# pcb.net
KiCad netlist of a schematic drawn in EAGLE
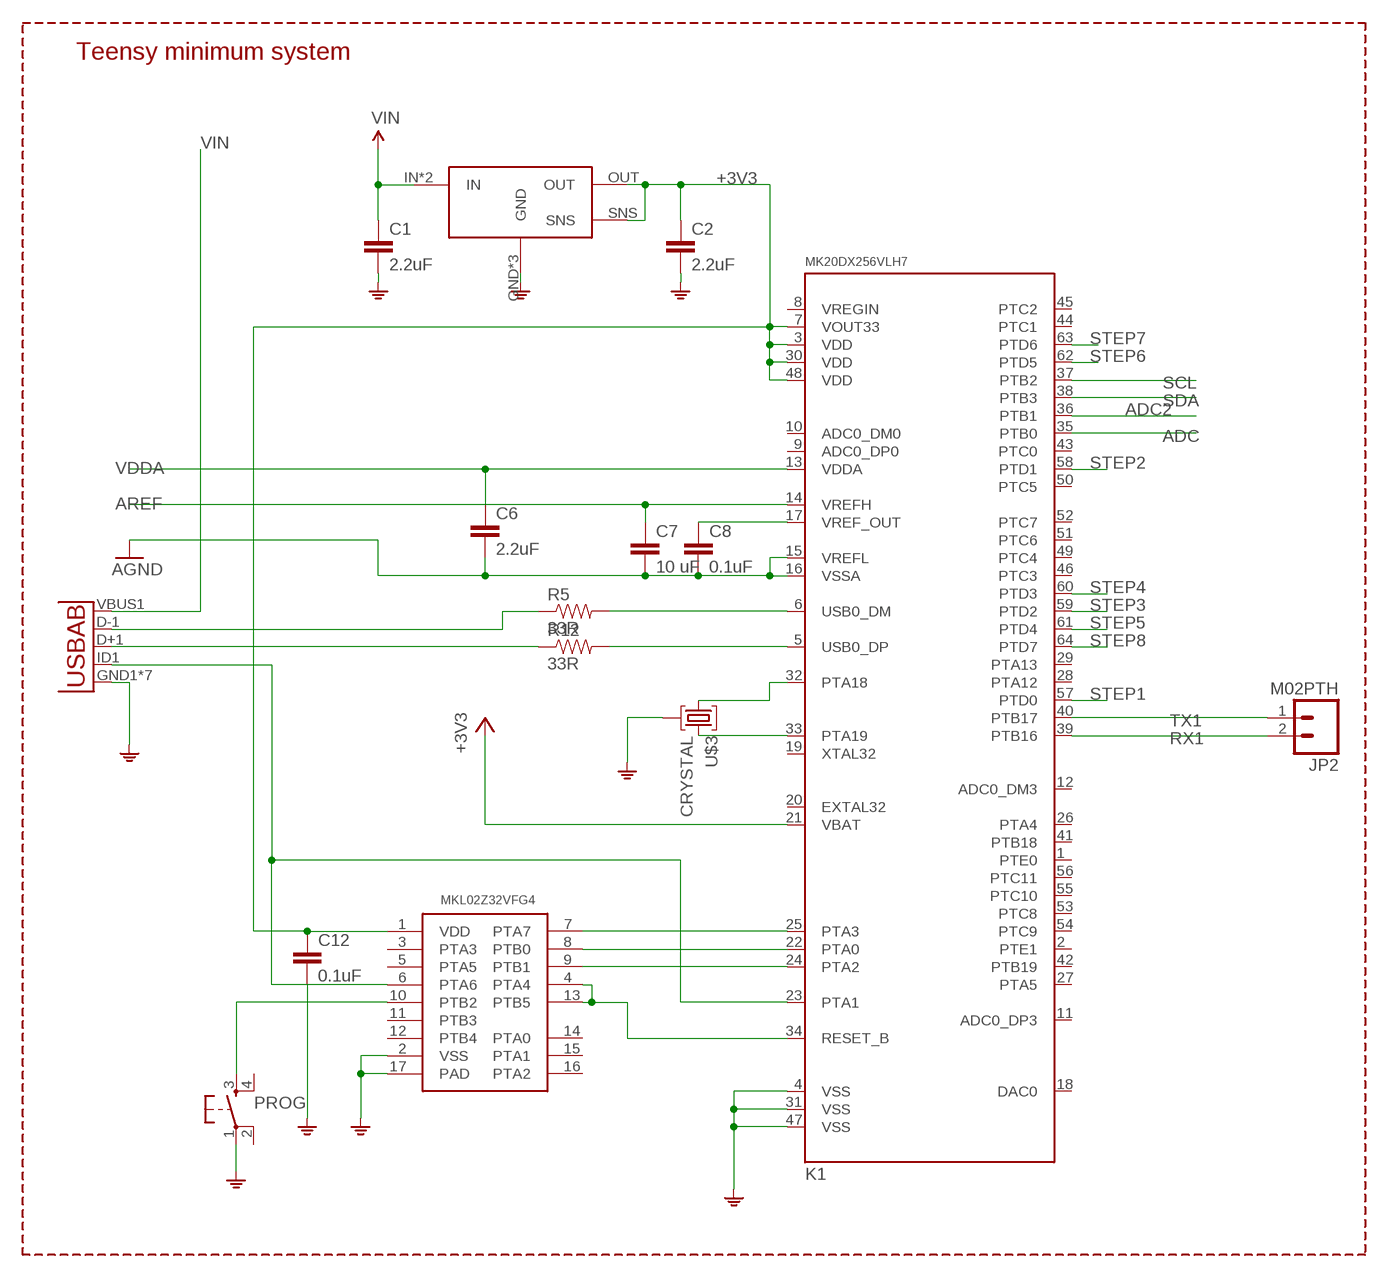
[diagram p0: schematic, sheet 1, part 1 of 2]
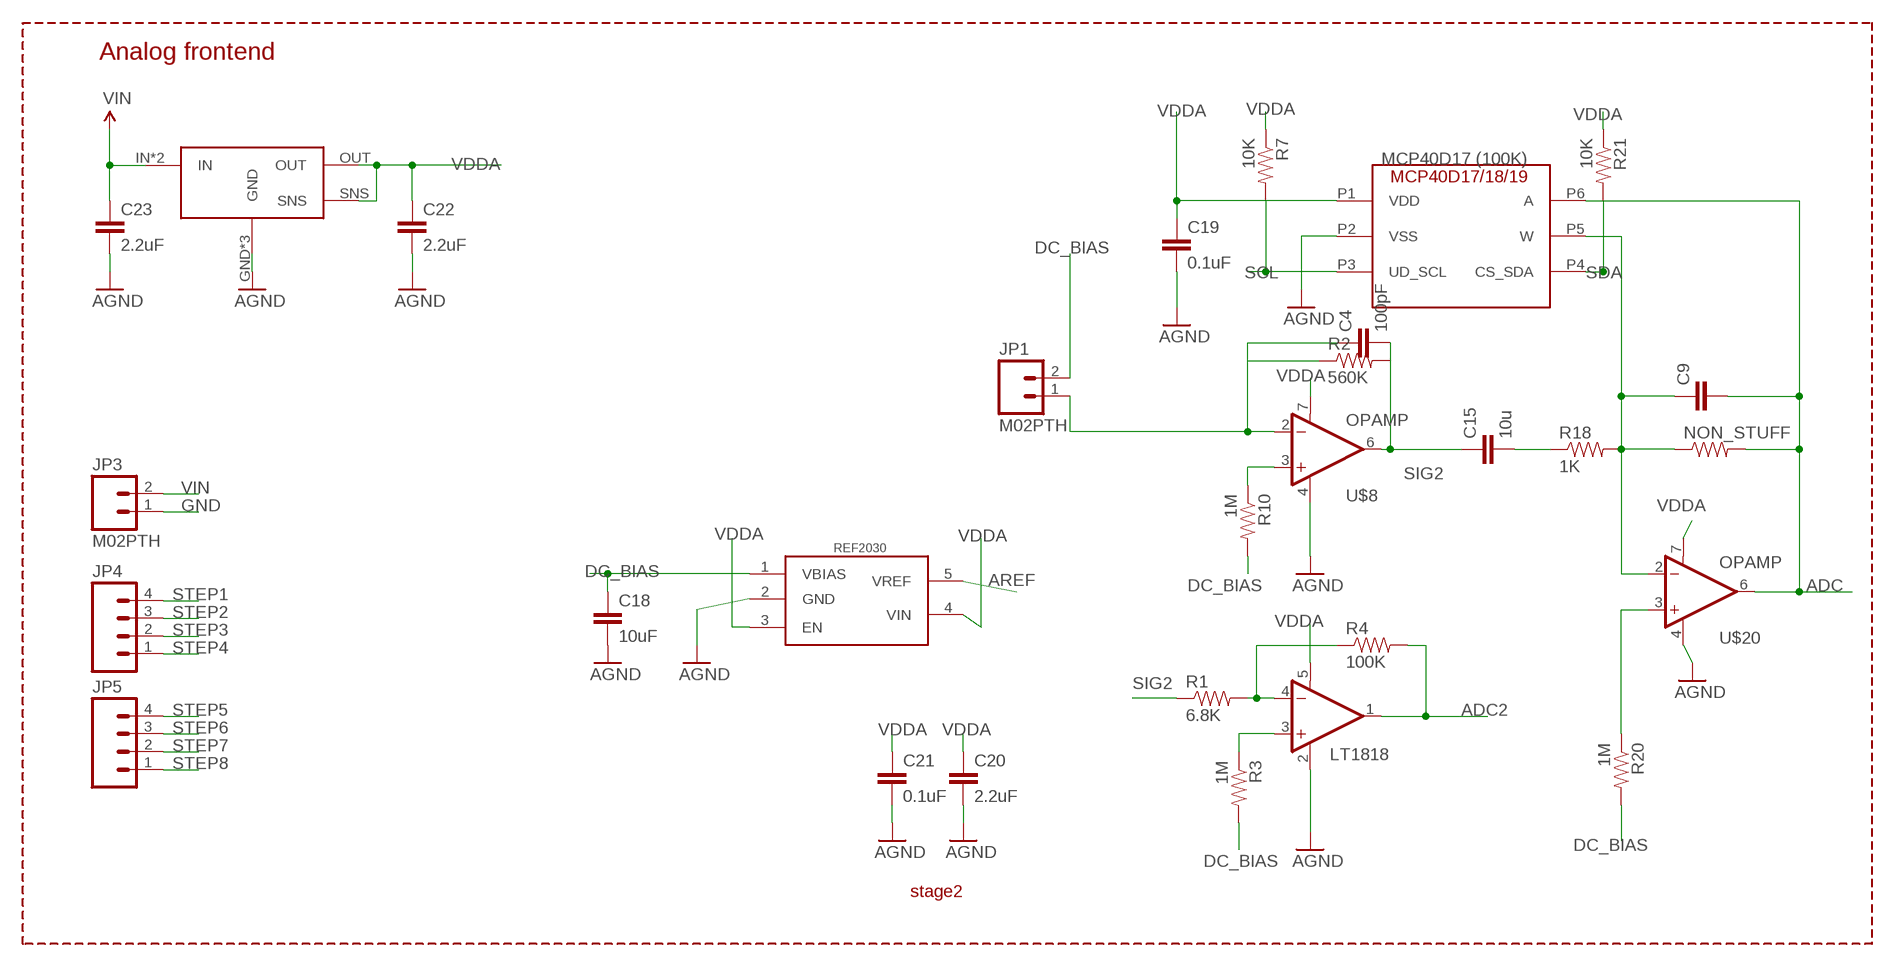
[diagram p1: schematic, sheet 1, part 2 of 2]

(export (version "E")
  (design (tool "Eeschema 10.0.6"))
  (components
    (comp (ref "C1")
      (value "2.2uF")
      (footprint "eagle-import:0402-CAP")
      (libsource (lib "eagle-import") (part "0.1UF-16V(+-10%)(0402)"))
    )
    (comp (ref "C2")
      (value "2.2uF")
      (footprint "eagle-import:0402-CAP")
      (libsource (lib "eagle-import") (part "0.1UF-16V(+-10%)(0402)"))
    )
    (comp (ref "C4")
      (value "100pF")
      (footprint "eagle-import:0402-CAP")
      (libsource (lib "eagle-import") (part "0.1UF-16V(+-10%)(0402)"))
    )
    (comp (ref "C6")
      (value "2.2uF")
      (footprint "eagle-import:0402-CAP")
      (libsource (lib "eagle-import") (part "0.1UF-16V(+-10%)(0402)"))
    )
    (comp (ref "C7")
      (value "10 uF")
      (footprint "eagle-import:0402-CAP")
      (libsource (lib "eagle-import") (part "0.1UF-16V(+-10%)(0402)"))
    )
    (comp (ref "C8")
      (value "0.1uF")
      (footprint "eagle-import:0402-CAP")
      (libsource (lib "eagle-import") (part "0.1UF-16V(+-10%)(0402)"))
    )
    (comp (ref "C9")
      (value "C-EUC0402")
      (footprint "eagle-import:C0402")
      (libsource (lib "eagle-import") (part "C-EUC0402"))
    )
    (comp (ref "C12")
      (value "0.1uF")
      (footprint "eagle-import:0402-CAP")
      (libsource (lib "eagle-import") (part "0.1UF-16V(+-10%)(0402)"))
    )
    (comp (ref "C15")
      (value "10u")
      (footprint "eagle-import:C0402")
      (libsource (lib "eagle-import") (part "C-EUC0402"))
    )
    (comp (ref "C18")
      (value "10uF")
      (footprint "eagle-import:0402-CAP")
      (libsource (lib "eagle-import") (part "0.1UF-16V(+-10%)(0402)"))
    )
    (comp (ref "C19")
      (value "0.1uF")
      (footprint "eagle-import:0402-CAP")
      (libsource (lib "eagle-import") (part "0.1UF-16V(+-10%)(0402)"))
    )
    (comp (ref "C20")
      (value "2.2uF")
      (footprint "eagle-import:0603-CAP")
      (libsource (lib "eagle-import") (part "0.1UF-25V(+80/-20%)(0603)"))
    )
    (comp (ref "C21")
      (value "0.1uF")
      (footprint "eagle-import:0402-CAP")
      (libsource (lib "eagle-import") (part "0.1UF-16V(+-10%)(0402)"))
    )
    (comp (ref "C22")
      (value "2.2uF")
      (footprint "eagle-import:0402-CAP")
      (libsource (lib "eagle-import") (part "0.1UF-16V(+-10%)(0402)"))
    )
    (comp (ref "C23")
      (value "2.2uF")
      (footprint "eagle-import:0402-CAP")
      (libsource (lib "eagle-import") (part "0.1UF-16V(+-10%)(0402)"))
    )
    (comp (ref "JP1")
      (value "M02PTH")
      (footprint "eagle-import:1X02")
      (libsource (lib "eagle-import") (part "M02PTH"))
    )
    (comp (ref "JP2")
      (value "M02PTH")
      (footprint "eagle-import:1X02")
      (libsource (lib "eagle-import") (part "M02PTH"))
    )
    (comp (ref "JP3")
      (value "M02PTH")
      (footprint "eagle-import:1X02")
      (libsource (lib "eagle-import") (part "M02PTH"))
    )
    (comp (ref "JP4")
      (value "M04PTH")
      (footprint "eagle-import:1X04")
      (libsource (lib "eagle-import") (part "M04PTH"))
    )
    (comp (ref "JP5")
      (value "M04PTH")
      (footprint "eagle-import:1X04")
      (libsource (lib "eagle-import") (part "M04PTH"))
    )
    (comp (ref "K1")
      (value "MK20DX256VLH7")
      (footprint "eagle-import:LQFP64-05")
      (fields (field (name "MF") "NXP"))
      (libsource (lib "eagle-import") (part "MK20DX256VLH7"))
    )
    (comp (ref "LP1")
      (value "LP38691SD")
      (footprint "eagle-import:WSON_6")
      (libsource (lib "eagle-import") (part "LP38691SD"))
    )
    (comp (ref "LP38691")
      (value "LP38691SD")
      (footprint "eagle-import:WSON_6")
      (libsource (lib "eagle-import") (part "LP38691SD"))
    )
    (comp (ref "NON_STUFF")
      (value "RESISTOR0402")
      (footprint "eagle-import:0402-RES")
      (libsource (lib "eagle-import") (part "RESISTOR0402"))
    )
    (comp (ref "PROG")
      (value "KMR211GLFS")
      (footprint "eagle-import:TACTILE_SWITCH_SMD")
      (libsource (lib "eagle-import") (part "TAC_SWITCHSMD"))
    )
    (comp (ref "R1")
      (value "6.8K")
      (footprint "eagle-import:0402-RES")
      (libsource (lib "eagle-import") (part "RESISTOR0402"))
    )
    (comp (ref "R2")
      (value "560K")
      (footprint "eagle-import:0402-RES")
      (libsource (lib "eagle-import") (part "RESISTOR0402"))
    )
    (comp (ref "R3")
      (value "1M")
      (footprint "eagle-import:0402-RES")
      (libsource (lib "eagle-import") (part "RESISTOR0402"))
    )
    (comp (ref "R4")
      (value "100K")
      (footprint "eagle-import:0402-RES")
      (libsource (lib "eagle-import") (part "RESISTOR0402"))
    )
    (comp (ref "R5")
      (value "33R")
      (footprint "eagle-import:0402-RES")
      (libsource (lib "eagle-import") (part "22OHM1/10W1%(0402)"))
    )
    (comp (ref "R7")
      (value "10K")
      (footprint "eagle-import:0402-RES")
      (libsource (lib "eagle-import") (part "RESISTOR0402"))
    )
    (comp (ref "R10")
      (value "1M")
      (footprint "eagle-import:0402-RES")
      (libsource (lib "eagle-import") (part "RESISTOR0402"))
    )
    (comp (ref "R12")
      (value "33R")
      (footprint "eagle-import:0402-RES")
      (libsource (lib "eagle-import") (part "22OHM1/10W1%(0402)"))
    )
    (comp (ref "R18")
      (value "1K")
      (footprint "eagle-import:0402-RES")
      (libsource (lib "eagle-import") (part "RESISTOR0402"))
    )
    (comp (ref "R20")
      (value "1M")
      (footprint "eagle-import:0402-RES")
      (libsource (lib "eagle-import") (part "RESISTOR0402"))
    )
    (comp (ref "R21")
      (value "10K")
      (footprint "eagle-import:0402-RES")
      (libsource (lib "eagle-import") (part "RESISTOR0402"))
    )
    (comp (ref "REF2030")
      (value "REF2033")
      (footprint "eagle-import:SOT23")
      (libsource (lib "eagle-import") (part "REF2033"))
    )
    (comp (ref "U$3")
      (value "CRYSTAL")
      (footprint "eagle-import:CRYSTAL")
      (libsource (lib "eagle-import") (part "CRYSTAL"))
    )
    (comp (ref "U$6")
      (value "MCP40D17/18/19")
      (footprint "eagle-import:SC70-6")
      (libsource (lib "eagle-import") (part "MCP40D17/18/19"))
    )
    (comp (ref "U$8")
      (value "OPAMP")
      (footprint "eagle-import:8-SOIC")
      (libsource (lib "eagle-import") (part "OPAMP"))
    )
    (comp (ref "U$14")
      (value "MKL02Z32VFG4_")
      (footprint "eagle-import:QFN16_3X3")
      (libsource (lib "eagle-import") (part "MKL02Z32VFG4_"))
    )
    (comp (ref "U$20")
      (value "OPAMP")
      (footprint "eagle-import:8-SOIC")
      (libsource (lib "eagle-import") (part "OPAMP"))
    )
    (comp (ref "U5")
      (value "USB\"\"")
      (footprint "eagle-import:USB-MICRO-SMD")
      (libsource (lib "eagle-import") (part "USB{dblquote}{dblquote}"))
    )
    (comp (ref "U14")
      (value "LT1818")
      (footprint "eagle-import:SOT23-5")
      (libsource (lib "eagle-import") (part "OPA344"))
    )
  )
  (nets
    (net (code "1") (name "+3V3") (class "Default")
      (node (ref "C12") (pin "1") (pinfunction "1_1") (pintype "passive"))
      (node (ref "C2") (pin "1") (pinfunction "1_1") (pintype "passive"))
      (node (ref "K1") (pin "21") (pinfunction "VBAT_21") (pintype "bidirectional"))
      (node (ref "K1") (pin "3") (pinfunction "VDD_3") (pintype "bidirectional"))
      (node (ref "K1") (pin "30") (pinfunction "VDD_30") (pintype "bidirectional"))
      (node (ref "K1") (pin "48") (pinfunction "VDD_48") (pintype "bidirectional"))
      (node (ref "K1") (pin "7") (pinfunction "VOUT33_7") (pintype "bidirectional"))
      (node (ref "LP38691") (pin "OUT") (pinfunction "OUT_OUT") (pintype "bidirectional"))
      (node (ref "LP38691") (pin "SNS") (pinfunction "SNS_SNS") (pintype "bidirectional"))
      (node (ref "U$14") (pin "1") (pinfunction "VDD_1") (pintype "bidirectional"))
    )
    (net (code "2") (name "/ADC") (class "Default")
      (node (ref "C9") (pin "2") (pinfunction "2_2") (pintype "passive"))
      (node (ref "K1") (pin "35") (pinfunction "PTB0_35") (pintype "bidirectional"))
      (node (ref "NON_STUFF") (pin "2") (pinfunction "2_2") (pintype "passive"))
      (node (ref "U$20") (pin "6") (pinfunction "OUT_6") (pintype "output"))
      (node (ref "U$6") (pin "P6") (pinfunction "A_P6") (pintype "bidirectional"))
    )
    (net (code "3") (name "/ADC2") (class "Default")
      (node (ref "K1") (pin "36") (pinfunction "PTB1_36") (pintype "bidirectional"))
      (node (ref "R4") (pin "2") (pinfunction "2_2") (pintype "passive"))
      (node (ref "U14") (pin "1") (pinfunction "OUT_1") (pintype "output"))
    )
    (net (code "4") (name "/AREF") (class "Default")
      (node (ref "C7") (pin "1") (pinfunction "1_1") (pintype "passive"))
      (node (ref "K1") (pin "14") (pinfunction "VREFH_14") (pintype "bidirectional"))
      (node (ref "REF2030") (pin "5") (pinfunction "VREF_5") (pintype "bidirectional"))
    )
    (net (code "5") (name "/DC_BIAS") (class "Default")
      (node (ref "C18") (pin "1") (pinfunction "1_1") (pintype "passive"))
      (node (ref "JP1") (pin "2") (pinfunction "2_2") (pintype "passive"))
      (node (ref "R10") (pin "2") (pinfunction "2_2") (pintype "passive"))
      (node (ref "R20") (pin "2") (pinfunction "2_2") (pintype "passive"))
      (node (ref "R3") (pin "2") (pinfunction "2_2") (pintype "passive"))
      (node (ref "REF2030") (pin "1") (pinfunction "VBIAS_1") (pintype "bidirectional"))
    )
    (net (code "6") (name "/RX1") (class "Default")
      (node (ref "JP2") (pin "2") (pinfunction "2_2") (pintype "passive"))
      (node (ref "K1") (pin "39") (pinfunction "PTB16_39") (pintype "bidirectional"))
    )
    (net (code "7") (name "/SCL") (class "Default")
      (node (ref "K1") (pin "37") (pinfunction "PTB2_37") (pintype "bidirectional"))
      (node (ref "R7") (pin "2") (pinfunction "2_2") (pintype "passive"))
      (node (ref "U$6") (pin "P3") (pinfunction "UD_SCL_P3") (pintype "bidirectional"))
    )
    (net (code "8") (name "/SDA") (class "Default")
      (node (ref "K1") (pin "38") (pinfunction "PTB3_38") (pintype "bidirectional"))
      (node (ref "R21") (pin "2") (pinfunction "2_2") (pintype "passive"))
      (node (ref "U$6") (pin "P4") (pinfunction "CS_SDA_P4") (pintype "bidirectional"))
    )
    (net (code "9") (name "/SIG2") (class "Default")
      (node (ref "C15") (pin "1") (pinfunction "1_1") (pintype "passive"))
      (node (ref "C4") (pin "2") (pinfunction "2_2") (pintype "passive"))
      (node (ref "R1") (pin "1") (pinfunction "1_1") (pintype "passive"))
      (node (ref "R2") (pin "2") (pinfunction "2_2") (pintype "passive"))
      (node (ref "U$8") (pin "6") (pinfunction "OUT_6") (pintype "output"))
    )
    (net (code "10") (name "/STEP1") (class "Default")
      (node (ref "JP4") (pin "4") (pinfunction "4_4") (pintype "passive"))
      (node (ref "K1") (pin "57") (pinfunction "PTD0_57") (pintype "bidirectional"))
    )
    (net (code "11") (name "/STEP2") (class "Default")
      (node (ref "JP4") (pin "3") (pinfunction "3_3") (pintype "passive"))
      (node (ref "K1") (pin "58") (pinfunction "PTD1_58") (pintype "bidirectional"))
    )
    (net (code "12") (name "/STEP3") (class "Default")
      (node (ref "JP4") (pin "2") (pinfunction "2_2") (pintype "passive"))
      (node (ref "K1") (pin "59") (pinfunction "PTD2_59") (pintype "bidirectional"))
    )
    (net (code "13") (name "/STEP4") (class "Default")
      (node (ref "JP4") (pin "1") (pinfunction "1_1") (pintype "passive"))
      (node (ref "K1") (pin "60") (pinfunction "PTD3_60") (pintype "bidirectional"))
    )
    (net (code "14") (name "/STEP5") (class "Default")
      (node (ref "JP5") (pin "4") (pinfunction "4_4") (pintype "passive"))
      (node (ref "K1") (pin "61") (pinfunction "PTD4_61") (pintype "bidirectional"))
    )
    (net (code "15") (name "/STEP6") (class "Default")
      (node (ref "JP5") (pin "3") (pinfunction "3_3") (pintype "passive"))
      (node (ref "K1") (pin "62") (pinfunction "PTD5_62") (pintype "bidirectional"))
    )
    (net (code "16") (name "/STEP7") (class "Default")
      (node (ref "JP5") (pin "2") (pinfunction "2_2") (pintype "passive"))
      (node (ref "K1") (pin "63") (pinfunction "PTD6_63") (pintype "bidirectional"))
    )
    (net (code "17") (name "/STEP8") (class "Default")
      (node (ref "JP5") (pin "1") (pinfunction "1_1") (pintype "passive"))
      (node (ref "K1") (pin "64") (pinfunction "PTD7_64") (pintype "bidirectional"))
    )
    (net (code "18") (name "/TX1") (class "Default")
      (node (ref "JP2") (pin "1") (pinfunction "1_1") (pintype "passive"))
      (node (ref "K1") (pin "40") (pinfunction "PTB17_40") (pintype "bidirectional"))
    )
    (net (code "19") (name "/VDDA") (class "Default")
      (node (ref "C19") (pin "1") (pinfunction "1_1") (pintype "passive"))
      (node (ref "C20") (pin "1") (pinfunction "1_1") (pintype "passive"))
      (node (ref "C21") (pin "1") (pinfunction "1_1") (pintype "passive"))
      (node (ref "C22") (pin "1") (pinfunction "1_1") (pintype "passive"))
      (node (ref "C6") (pin "1") (pinfunction "1_1") (pintype "passive"))
      (node (ref "K1") (pin "13") (pinfunction "VDDA_13") (pintype "bidirectional"))
      (node (ref "LP1") (pin "OUT") (pinfunction "OUT_OUT") (pintype "bidirectional"))
      (node (ref "LP1") (pin "SNS") (pinfunction "SNS_SNS") (pintype "bidirectional"))
      (node (ref "R21") (pin "1") (pinfunction "1_1") (pintype "passive"))
      (node (ref "R7") (pin "1") (pinfunction "1_1") (pintype "passive"))
      (node (ref "REF2030") (pin "3") (pinfunction "EN_3") (pintype "bidirectional"))
      (node (ref "REF2030") (pin "4") (pinfunction "VIN_4") (pintype "bidirectional"))
      (node (ref "U$20") (pin "7") (pinfunction "V+_7") (pintype "power_in"))
      (node (ref "U$6") (pin "P1") (pinfunction "VDD_P1") (pintype "power_in"))
      (node (ref "U$8") (pin "7") (pinfunction "V+_7") (pintype "power_in"))
      (node (ref "U14") (pin "5") (pinfunction "V+_5") (pintype "power_in"))
    )
    (net (code "20") (name "AGND") (class "Default")
      (node (ref "C18") (pin "2") (pinfunction "2_2") (pintype "passive"))
      (node (ref "C19") (pin "2") (pinfunction "2_2") (pintype "passive"))
      (node (ref "C20") (pin "2") (pinfunction "2_2") (pintype "passive"))
      (node (ref "C21") (pin "2") (pinfunction "2_2") (pintype "passive"))
      (node (ref "C22") (pin "2") (pinfunction "2_2") (pintype "passive"))
      (node (ref "C23") (pin "2") (pinfunction "2_2") (pintype "passive"))
      (node (ref "C6") (pin "2") (pinfunction "2_2") (pintype "passive"))
      (node (ref "C7") (pin "2") (pinfunction "2_2") (pintype "passive"))
      (node (ref "C8") (pin "2") (pinfunction "2_2") (pintype "passive"))
      (node (ref "K1") (pin "15") (pinfunction "VREFL_15") (pintype "bidirectional"))
      (node (ref "K1") (pin "16") (pinfunction "VSSA_16") (pintype "bidirectional"))
      (node (ref "LP1") (pin "GND") (pinfunction "GND_GND") (pintype "bidirectional"))
      (node (ref "LP1") (pin "N/C") (pinfunction "GND_N/C") (pintype "bidirectional"))
      (node (ref "LP1") (pin "THERMAL") (pinfunction "GND_THERMAL") (pintype "bidirectional"))
      (node (ref "REF2030") (pin "2") (pinfunction "GND_2") (pintype "bidirectional"))
      (node (ref "U$20") (pin "4") (pinfunction "V-_4") (pintype "power_in"))
      (node (ref "U$6") (pin "P2") (pinfunction "VSS_P2") (pintype "power_in"))
      (node (ref "U$8") (pin "4") (pinfunction "V-_4") (pintype "power_in"))
      (node (ref "U14") (pin "2") (pinfunction "V-_2") (pintype "power_in"))
    )
    (net (code "21") (name "GND") (class "Default")
      (node (ref "C1") (pin "2") (pinfunction "2_2") (pintype "passive"))
      (node (ref "C12") (pin "2") (pinfunction "2_2") (pintype "passive"))
      (node (ref "C2") (pin "2") (pinfunction "2_2") (pintype "passive"))
      (node (ref "JP3") (pin "1") (pinfunction "1_1") (pintype "passive"))
      (node (ref "K1") (pin "31") (pinfunction "VSS_31") (pintype "bidirectional"))
      (node (ref "K1") (pin "4") (pinfunction "VSS_4") (pintype "bidirectional"))
      (node (ref "K1") (pin "47") (pinfunction "VSS_47") (pintype "bidirectional"))
      (node (ref "LP38691") (pin "GND") (pinfunction "GND_GND") (pintype "bidirectional"))
      (node (ref "LP38691") (pin "N/C") (pinfunction "GND_N/C") (pintype "bidirectional"))
      (node (ref "LP38691") (pin "THERMAL") (pinfunction "GND_THERMAL") (pintype "bidirectional"))
      (node (ref "PROG") (pin "1") (pinfunction "1_1") (pintype "passive"))
      (node (ref "U$14") (pin "17") (pinfunction "PAD_17") (pintype "bidirectional"))
      (node (ref "U$14") (pin "2") (pinfunction "VSS_2") (pintype "bidirectional"))
      (node (ref "U$3") (pin "GND1") (pinfunction "2_GND1") (pintype "passive"))
      (node (ref "U$3") (pin "GND2") (pinfunction "2_GND2") (pintype "passive"))
      (node (ref "U5") (pin "GND1") (pinfunction "GND_GND1") (pintype "bidirectional"))
      (node (ref "U5") (pin "P$1") (pinfunction "GND_P$1") (pintype "bidirectional"))
      (node (ref "U5") (pin "P$2") (pinfunction "GND_P$2") (pintype "bidirectional"))
      (node (ref "U5") (pin "P$3") (pinfunction "GND_P$3") (pintype "bidirectional"))
      (node (ref "U5") (pin "P$4") (pinfunction "GND_P$4") (pintype "bidirectional"))
      (node (ref "U5") (pin "P$5") (pinfunction "GND_P$5") (pintype "bidirectional"))
      (node (ref "U5") (pin "P$6") (pinfunction "GND_P$6") (pintype "bidirectional"))
    )
    (net (code "22") (name "Net-(C15-Pad2)") (class "Default")
      (node (ref "C15") (pin "2") (pinfunction "2_2") (pintype "passive"))
      (node (ref "R18") (pin "1") (pinfunction "1_1") (pintype "passive"))
    )
    (net (code "23") (name "Net-(K1-PTA0)") (class "Default")
      (node (ref "K1") (pin "22") (pinfunction "PTA0_22") (pintype "bidirectional"))
      (node (ref "U$14") (pin "8") (pinfunction "PTB0_8") (pintype "bidirectional"))
    )
    (net (code "24") (name "Net-(K1-PTA1)") (class "Default")
      (node (ref "K1") (pin "23") (pinfunction "PTA1_23") (pintype "bidirectional"))
      (node (ref "U$14") (pin "6") (pinfunction "PTA6_6") (pintype "bidirectional"))
      (node (ref "U5") (pin "ID1") (pinfunction "USBID_ID1") (pintype "bidirectional"))
    )
    (net (code "25") (name "Net-(K1-PTA2)") (class "Default")
      (node (ref "K1") (pin "24") (pinfunction "PTA2_24") (pintype "bidirectional"))
      (node (ref "U$14") (pin "9") (pinfunction "PTB1_9") (pintype "bidirectional"))
    )
    (net (code "26") (name "Net-(K1-PTA3)") (class "Default")
      (node (ref "K1") (pin "25") (pinfunction "PTA3_25") (pintype "bidirectional"))
      (node (ref "U$14") (pin "7") (pinfunction "PTA7_7") (pintype "bidirectional"))
    )
    (net (code "27") (name "Net-(K1-PTA18)") (class "Default")
      (node (ref "K1") (pin "32") (pinfunction "PTA18_32") (pintype "bidirectional"))
      (node (ref "U$3") (pin "SIG1") (pinfunction "1_SIG1") (pintype "passive"))
    )
    (net (code "28") (name "Net-(K1-PTA19)") (class "Default")
      (node (ref "K1") (pin "33") (pinfunction "PTA19_33") (pintype "bidirectional"))
      (node (ref "U$3") (pin "SIG2") (pinfunction "3_SIG2") (pintype "passive"))
    )
    (net (code "29") (name "Net-(K1-RESET_B)") (class "Default")
      (node (ref "K1") (pin "34") (pinfunction "RESET_B_34") (pintype "bidirectional"))
      (node (ref "U$14") (pin "13") (pinfunction "PTB5_13") (pintype "bidirectional"))
      (node (ref "U$14") (pin "4") (pinfunction "PTA4_4") (pintype "bidirectional"))
    )
    (net (code "30") (name "Net-(K1-USB0_DM)") (class "Default")
      (node (ref "K1") (pin "6") (pinfunction "USB0_DM_6") (pintype "bidirectional"))
      (node (ref "R5") (pin "2") (pinfunction "2_2") (pintype "passive"))
    )
    (net (code "31") (name "Net-(K1-USB0_DP)") (class "Default")
      (node (ref "K1") (pin "5") (pinfunction "USB0_DP_5") (pintype "bidirectional"))
      (node (ref "R12") (pin "2") (pinfunction "2_2") (pintype "passive"))
    )
    (net (code "32") (name "Net-(K1-VREF_OUT)") (class "Default")
      (node (ref "C8") (pin "1") (pinfunction "1_1") (pintype "passive"))
      (node (ref "K1") (pin "17") (pinfunction "VREF_OUT_17") (pintype "bidirectional"))
    )
    (net (code "33") (name "Net-(U$8-+IN)") (class "Default")
      (node (ref "R10") (pin "1") (pinfunction "1_1") (pintype "passive"))
      (node (ref "U$8") (pin "3") (pinfunction "+IN_3") (pintype "input"))
    )
    (net (code "34") (name "Net-(U$8--IN)") (class "Default")
      (node (ref "C4") (pin "1") (pinfunction "1_1") (pintype "passive"))
      (node (ref "JP1") (pin "1") (pinfunction "1_1") (pintype "passive"))
      (node (ref "R2") (pin "1") (pinfunction "1_1") (pintype "passive"))
      (node (ref "U$8") (pin "2") (pinfunction "-IN_2") (pintype "input"))
    )
    (net (code "35") (name "Net-(U$14-PTB2)") (class "Default")
      (node (ref "PROG") (pin "3") (pinfunction "3_3") (pintype "passive"))
      (node (ref "U$14") (pin "10") (pinfunction "PTB2_10") (pintype "bidirectional"))
    )
    (net (code "36") (name "Net-(U$20-+IN)") (class "Default")
      (node (ref "R20") (pin "1") (pinfunction "1_1") (pintype "passive"))
      (node (ref "U$20") (pin "3") (pinfunction "+IN_3") (pintype "input"))
    )
    (net (code "37") (name "Net-(U$20--IN)") (class "Default")
      (node (ref "C9") (pin "1") (pinfunction "1_1") (pintype "passive"))
      (node (ref "NON_STUFF") (pin "1") (pinfunction "1_1") (pintype "passive"))
      (node (ref "R18") (pin "2") (pinfunction "2_2") (pintype "passive"))
      (node (ref "U$20") (pin "2") (pinfunction "-IN_2") (pintype "input"))
      (node (ref "U$6") (pin "P5") (pinfunction "W_P5") (pintype "bidirectional"))
    )
    (net (code "38") (name "Net-(U5-D+)") (class "Default")
      (node (ref "R12") (pin "1") (pinfunction "1_1") (pintype "passive"))
      (node (ref "U5") (pin "D+1") (pinfunction "D+_D+1") (pintype "bidirectional"))
    )
    (net (code "39") (name "Net-(U5-D-)") (class "Default")
      (node (ref "R5") (pin "1") (pinfunction "1_1") (pintype "passive"))
      (node (ref "U5") (pin "D-1") (pinfunction "D-_D-1") (pintype "bidirectional"))
    )
    (net (code "40") (name "Net-(U14-+IN)") (class "Default")
      (node (ref "R3") (pin "1") (pinfunction "1_1") (pintype "passive"))
      (node (ref "U14") (pin "3") (pinfunction "+IN_3") (pintype "input"))
    )
    (net (code "41") (name "Net-(U14--IN)") (class "Default")
      (node (ref "R1") (pin "2") (pinfunction "2_2") (pintype "passive"))
      (node (ref "R4") (pin "1") (pinfunction "1_1") (pintype "passive"))
      (node (ref "U14") (pin "4") (pinfunction "-IN_4") (pintype "input"))
    )
    (net (code "42") (name "VIN") (class "Default")
      (node (ref "C1") (pin "1") (pinfunction "1_1") (pintype "passive"))
      (node (ref "C23") (pin "1") (pinfunction "1_1") (pintype "passive"))
      (node (ref "JP3") (pin "2") (pinfunction "2_2") (pintype "passive"))
      (node (ref "LP1") (pin "IN") (pinfunction "IN_IN") (pintype "bidirectional"))
      (node (ref "LP1") (pin "IN2") (pinfunction "IN_IN2") (pintype "bidirectional"))
      (node (ref "LP38691") (pin "IN") (pinfunction "IN_IN") (pintype "bidirectional"))
      (node (ref "LP38691") (pin "IN2") (pinfunction "IN_IN2") (pintype "bidirectional"))
      (node (ref "U5") (pin "VBUS1") (pinfunction "VBUS_VBUS1") (pintype "bidirectional"))
    )
    (net (code "43") (name "unconnected-(K1-ADC0_DM0-Pad10)") (class "Default")
      (node (ref "K1") (pin "10") (pinfunction "ADC0_DM0_10") (pintype "bidirectional"))
    )
    (net (code "44") (name "unconnected-(K1-ADC0_DM3-Pad12)") (class "Default")
      (node (ref "K1") (pin "12") (pinfunction "ADC0_DM3_12") (pintype "bidirectional"))
    )
    (net (code "45") (name "unconnected-(K1-ADC0_DP0-Pad9)") (class "Default")
      (node (ref "K1") (pin "9") (pinfunction "ADC0_DP0_9") (pintype "bidirectional"))
    )
    (net (code "46") (name "unconnected-(K1-ADC0_DP3-Pad11)") (class "Default")
      (node (ref "K1") (pin "11") (pinfunction "ADC0_DP3_11") (pintype "bidirectional"))
    )
    (net (code "47") (name "unconnected-(K1-DAC0-Pad18)") (class "Default")
      (node (ref "K1") (pin "18") (pinfunction "DAC0_18") (pintype "bidirectional"))
    )
    (net (code "48") (name "unconnected-(K1-EXTAL32-Pad20)") (class "Default")
      (node (ref "K1") (pin "20") (pinfunction "EXTAL32_20") (pintype "bidirectional"))
    )
    (net (code "49") (name "unconnected-(K1-PTA4-Pad26)") (class "Default")
      (node (ref "K1") (pin "26") (pinfunction "PTA4_26") (pintype "bidirectional"))
    )
    (net (code "50") (name "unconnected-(K1-PTA5-Pad27)") (class "Default")
      (node (ref "K1") (pin "27") (pinfunction "PTA5_27") (pintype "bidirectional"))
    )
    (net (code "51") (name "unconnected-(K1-PTA12-Pad28)") (class "Default")
      (node (ref "K1") (pin "28") (pinfunction "PTA12_28") (pintype "bidirectional"))
    )
    (net (code "52") (name "unconnected-(K1-PTA13-Pad29)") (class "Default")
      (node (ref "K1") (pin "29") (pinfunction "PTA13_29") (pintype "bidirectional"))
    )
    (net (code "53") (name "unconnected-(K1-PTB18-Pad41)") (class "Default")
      (node (ref "K1") (pin "41") (pinfunction "PTB18_41") (pintype "bidirectional"))
    )
    (net (code "54") (name "unconnected-(K1-PTB19-Pad42)") (class "Default")
      (node (ref "K1") (pin "42") (pinfunction "PTB19_42") (pintype "bidirectional"))
    )
    (net (code "55") (name "unconnected-(K1-PTC0-Pad43)") (class "Default")
      (node (ref "K1") (pin "43") (pinfunction "PTC0_43") (pintype "bidirectional"))
    )
    (net (code "56") (name "unconnected-(K1-PTC1-Pad44)") (class "Default")
      (node (ref "K1") (pin "44") (pinfunction "PTC1_44") (pintype "bidirectional"))
    )
    (net (code "57") (name "unconnected-(K1-PTC2-Pad45)") (class "Default")
      (node (ref "K1") (pin "45") (pinfunction "PTC2_45") (pintype "bidirectional"))
    )
    (net (code "58") (name "unconnected-(K1-PTC3-Pad46)") (class "Default")
      (node (ref "K1") (pin "46") (pinfunction "PTC3_46") (pintype "bidirectional"))
    )
    (net (code "59") (name "unconnected-(K1-PTC4-Pad49)") (class "Default")
      (node (ref "K1") (pin "49") (pinfunction "PTC4_49") (pintype "bidirectional"))
    )
    (net (code "60") (name "unconnected-(K1-PTC5-Pad50)") (class "Default")
      (node (ref "K1") (pin "50") (pinfunction "PTC5_50") (pintype "bidirectional"))
    )
    (net (code "61") (name "unconnected-(K1-PTC6-Pad51)") (class "Default")
      (node (ref "K1") (pin "51") (pinfunction "PTC6_51") (pintype "bidirectional"))
    )
    (net (code "62") (name "unconnected-(K1-PTC7-Pad52)") (class "Default")
      (node (ref "K1") (pin "52") (pinfunction "PTC7_52") (pintype "bidirectional"))
    )
    (net (code "63") (name "unconnected-(K1-PTC8-Pad53)") (class "Default")
      (node (ref "K1") (pin "53") (pinfunction "PTC8_53") (pintype "bidirectional"))
    )
    (net (code "64") (name "unconnected-(K1-PTC9-Pad54)") (class "Default")
      (node (ref "K1") (pin "54") (pinfunction "PTC9_54") (pintype "bidirectional"))
    )
    (net (code "65") (name "unconnected-(K1-PTC10-Pad55)") (class "Default")
      (node (ref "K1") (pin "55") (pinfunction "PTC10_55") (pintype "bidirectional"))
    )
    (net (code "66") (name "unconnected-(K1-PTC11-Pad56)") (class "Default")
      (node (ref "K1") (pin "56") (pinfunction "PTC11_56") (pintype "bidirectional"))
    )
    (net (code "67") (name "unconnected-(K1-PTE0-Pad1)") (class "Default")
      (node (ref "K1") (pin "1") (pinfunction "PTE0_1") (pintype "bidirectional"))
    )
    (net (code "68") (name "unconnected-(K1-PTE1-Pad2)") (class "Default")
      (node (ref "K1") (pin "2") (pinfunction "PTE1_2") (pintype "bidirectional"))
    )
    (net (code "69") (name "unconnected-(K1-VREGIN-Pad8)") (class "Default")
      (node (ref "K1") (pin "8") (pinfunction "VREGIN_8") (pintype "bidirectional"))
    )
    (net (code "70") (name "unconnected-(K1-XTAL32-Pad19)") (class "Default")
      (node (ref "K1") (pin "19") (pinfunction "XTAL32_19") (pintype "bidirectional"))
    )
    (net (code "71") (name "unconnected-(PROG-Pad2)") (class "Default")
      (node (ref "PROG") (pin "2") (pinfunction "2_2") (pintype "passive"))
    )
    (net (code "72") (name "unconnected-(PROG-Pad4)") (class "Default")
      (node (ref "PROG") (pin "4") (pinfunction "4_4") (pintype "passive"))
    )
    (net (code "73") (name "unconnected-(U$14-PTA0-Pad14)") (class "Default")
      (node (ref "U$14") (pin "14") (pinfunction "PTA0_14") (pintype "bidirectional"))
    )
    (net (code "74") (name "unconnected-(U$14-PTA1-Pad15)") (class "Default")
      (node (ref "U$14") (pin "15") (pinfunction "PTA1_15") (pintype "bidirectional"))
    )
    (net (code "75") (name "unconnected-(U$14-PTA2-Pad16)") (class "Default")
      (node (ref "U$14") (pin "16") (pinfunction "PTA2_16") (pintype "bidirectional"))
    )
    (net (code "76") (name "unconnected-(U$14-PTA3-Pad3)") (class "Default")
      (node (ref "U$14") (pin "3") (pinfunction "PTA3_3") (pintype "bidirectional"))
    )
    (net (code "77") (name "unconnected-(U$14-PTA5-Pad5)") (class "Default")
      (node (ref "U$14") (pin "5") (pinfunction "PTA5_5") (pintype "bidirectional"))
    )
    (net (code "78") (name "unconnected-(U$14-PTB3-Pad11)") (class "Default")
      (node (ref "U$14") (pin "11") (pinfunction "PTB3_11") (pintype "bidirectional"))
    )
    (net (code "79") (name "unconnected-(U$14-PTB4-Pad12)") (class "Default")
      (node (ref "U$14") (pin "12") (pinfunction "PTB4_12") (pintype "bidirectional"))
    )
  )
)
